# raspi.net
KiCad netlist of a schematic drawn in EAGLE
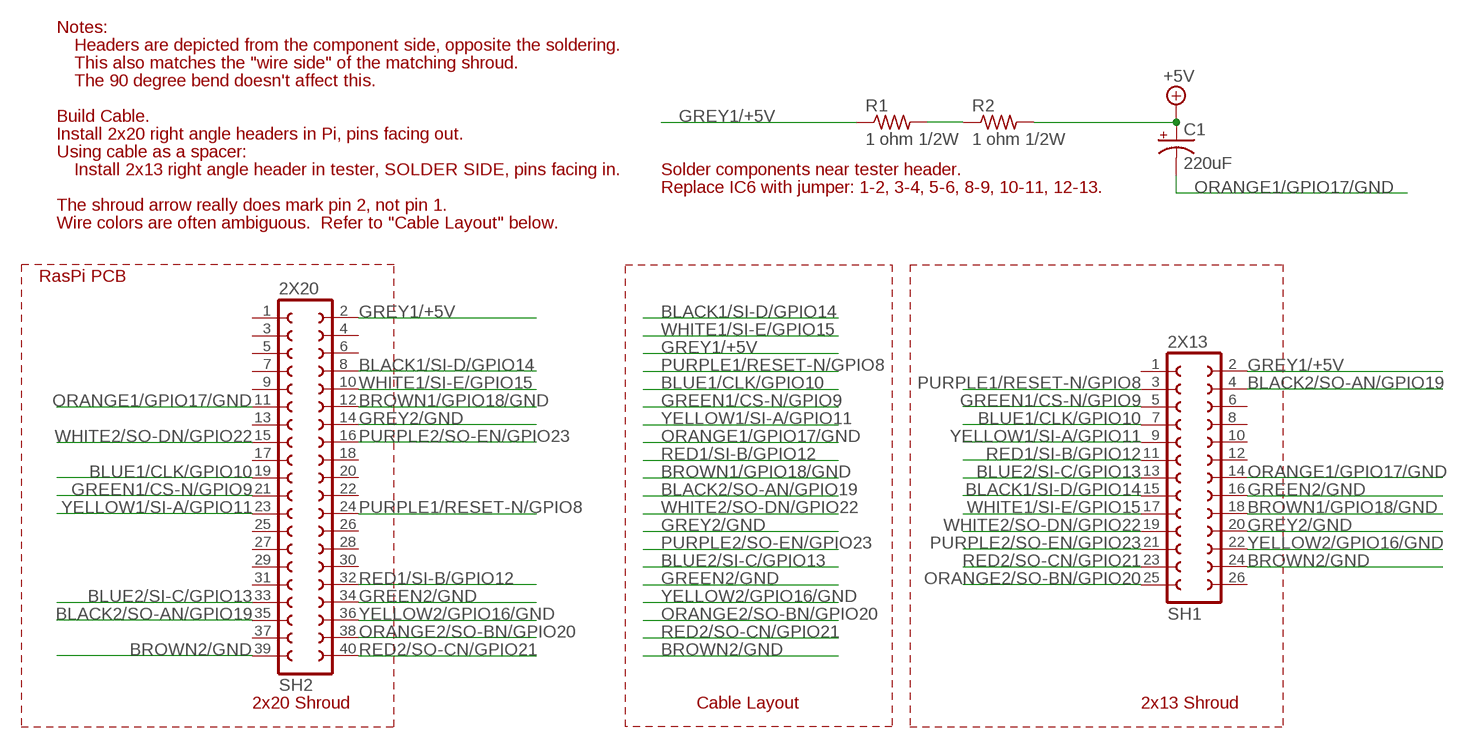
[diagram p0: schematic, sheet 1]

(export (version "E")
  (design (tool "Eeschema 10.0.6"))
  (components
    (comp (ref "C1")
      (value "220uF")
      (footprint "eagle-import:E15-6")
      (libsource (lib "eagle-import") (part "CPOL-USE15-6AXIAL"))
    )
    (comp (ref "R1")
      (value "1 ohm 1/2W")
      (footprint "eagle-import:0207_10")
      (libsource (lib "eagle-import") (part "R-US_0207/10"))
    )
    (comp (ref "R2")
      (value "1 ohm 1/2W")
      (footprint "eagle-import:0207_10")
      (libsource (lib "eagle-import") (part "R-US_0207/10"))
    )
    (comp (ref "SH1")
      (value "2X13")
      (footprint "eagle-import:FE13-2")
      (libsource (lib "eagle-import") (part "FE13-2"))
    )
    (comp (ref "SH2")
      (value "2X20")
      (footprint "eagle-import:FE20-2")
      (libsource (lib "eagle-import") (part "FE20-2"))
    )
  )
  (nets
    (net (code "1") (name "+5V") (class "Default")
      (node (ref "C1") (pin "+") (pinfunction "+_+") (pintype "passive"))
      (node (ref "R2") (pin "2") (pinfunction "2_2") (pintype "passive"))
    )
    (net (code "2") (name "/BLACK1{slash}SI-D{slash}GPIO14") (class "Default")
      (node (ref "SH1") (pin "15") (pinfunction "15_15") (pintype "passive"))
      (node (ref "SH2") (pin "8") (pinfunction "8_8") (pintype "passive"))
    )
    (net (code "3") (name "/BLACK2{slash}SO-AN{slash}GPIO19") (class "Default")
      (node (ref "SH1") (pin "4") (pinfunction "4_4") (pintype "passive"))
      (node (ref "SH2") (pin "35") (pinfunction "35_35") (pintype "passive"))
    )
    (net (code "4") (name "/BLUE1{slash}CLK{slash}GPIO10") (class "Default")
      (node (ref "SH1") (pin "7") (pinfunction "7_7") (pintype "passive"))
      (node (ref "SH2") (pin "19") (pinfunction "19_19") (pintype "passive"))
    )
    (net (code "5") (name "/BLUE2{slash}SI-C{slash}GPIO13") (class "Default")
      (node (ref "SH1") (pin "13") (pinfunction "13_13") (pintype "passive"))
      (node (ref "SH2") (pin "33") (pinfunction "33_33") (pintype "passive"))
    )
    (net (code "6") (name "/BROWN1{slash}GPIO18{slash}GND") (class "Default")
      (node (ref "SH1") (pin "18") (pinfunction "18_18") (pintype "passive"))
      (node (ref "SH2") (pin "12") (pinfunction "12_12") (pintype "passive"))
    )
    (net (code "7") (name "/BROWN2{slash}GND") (class "Default")
      (node (ref "SH1") (pin "24") (pinfunction "24_24") (pintype "passive"))
      (node (ref "SH2") (pin "39") (pinfunction "39_39") (pintype "passive"))
    )
    (net (code "8") (name "/GREEN1{slash}CS-N{slash}GPIO9") (class "Default")
      (node (ref "SH1") (pin "5") (pinfunction "5_5") (pintype "passive"))
      (node (ref "SH2") (pin "21") (pinfunction "21_21") (pintype "passive"))
    )
    (net (code "9") (name "/GREEN2{slash}GND") (class "Default")
      (node (ref "SH1") (pin "16") (pinfunction "16_16") (pintype "passive"))
      (node (ref "SH2") (pin "34") (pinfunction "34_34") (pintype "passive"))
    )
    (net (code "10") (name "/GREY1{slash}+5V") (class "Default")
      (node (ref "R1") (pin "1") (pinfunction "1_1") (pintype "passive"))
      (node (ref "SH1") (pin "2") (pinfunction "2_2") (pintype "passive"))
      (node (ref "SH2") (pin "2") (pinfunction "2_2") (pintype "passive"))
    )
    (net (code "11") (name "/GREY2{slash}GND") (class "Default")
      (node (ref "SH1") (pin "20") (pinfunction "20_20") (pintype "passive"))
      (node (ref "SH2") (pin "14") (pinfunction "14_14") (pintype "passive"))
    )
    (net (code "12") (name "/ORANGE1{slash}GPIO17{slash}GND") (class "Default")
      (node (ref "C1") (pin "-") (pinfunction "-_-") (pintype "passive"))
      (node (ref "SH1") (pin "14") (pinfunction "14_14") (pintype "passive"))
      (node (ref "SH2") (pin "11") (pinfunction "11_11") (pintype "passive"))
    )
    (net (code "13") (name "/ORANGE2{slash}SO-BN{slash}GPIO20") (class "Default")
      (node (ref "SH1") (pin "25") (pinfunction "25_25") (pintype "passive"))
      (node (ref "SH2") (pin "38") (pinfunction "38_38") (pintype "passive"))
    )
    (net (code "14") (name "/PURPLE1{slash}RESET-N{slash}GPIO8") (class "Default")
      (node (ref "SH1") (pin "3") (pinfunction "3_3") (pintype "passive"))
      (node (ref "SH2") (pin "24") (pinfunction "24_24") (pintype "passive"))
    )
    (net (code "15") (name "/PURPLE2{slash}SO-EN{slash}GPIO23") (class "Default")
      (node (ref "SH1") (pin "21") (pinfunction "21_21") (pintype "passive"))
      (node (ref "SH2") (pin "16") (pinfunction "16_16") (pintype "passive"))
    )
    (net (code "16") (name "/RED1{slash}SI-B{slash}GPIO12") (class "Default")
      (node (ref "SH1") (pin "11") (pinfunction "11_11") (pintype "passive"))
      (node (ref "SH2") (pin "32") (pinfunction "32_32") (pintype "passive"))
    )
    (net (code "17") (name "/RED2{slash}SO-CN{slash}GPIO21") (class "Default")
      (node (ref "SH1") (pin "23") (pinfunction "23_23") (pintype "passive"))
      (node (ref "SH2") (pin "40") (pinfunction "40_40") (pintype "passive"))
    )
    (net (code "18") (name "/WHITE1{slash}SI-E{slash}GPIO15") (class "Default")
      (node (ref "SH1") (pin "17") (pinfunction "17_17") (pintype "passive"))
      (node (ref "SH2") (pin "10") (pinfunction "10_10") (pintype "passive"))
    )
    (net (code "19") (name "/WHITE2{slash}SO-DN{slash}GPIO22") (class "Default")
      (node (ref "SH1") (pin "19") (pinfunction "19_19") (pintype "passive"))
      (node (ref "SH2") (pin "15") (pinfunction "15_15") (pintype "passive"))
    )
    (net (code "20") (name "/YELLOW1{slash}SI-A{slash}GPIO11") (class "Default")
      (node (ref "SH1") (pin "9") (pinfunction "9_9") (pintype "passive"))
      (node (ref "SH2") (pin "23") (pinfunction "23_23") (pintype "passive"))
    )
    (net (code "21") (name "/YELLOW2{slash}GPIO16{slash}GND") (class "Default")
      (node (ref "SH1") (pin "22") (pinfunction "22_22") (pintype "passive"))
      (node (ref "SH2") (pin "36") (pinfunction "36_36") (pintype "passive"))
    )
    (net (code "22") (name "Net-(R1-Pad2)") (class "Default")
      (node (ref "R1") (pin "2") (pinfunction "2_2") (pintype "passive"))
      (node (ref "R2") (pin "1") (pinfunction "1_1") (pintype "passive"))
    )
    (net (code "23") (name "unconnected-(SH1-Pad1)") (class "Default")
      (node (ref "SH1") (pin "1") (pinfunction "1_1") (pintype "passive"))
    )
    (net (code "24") (name "unconnected-(SH1-Pad6)") (class "Default")
      (node (ref "SH1") (pin "6") (pinfunction "6_6") (pintype "passive"))
    )
    (net (code "25") (name "unconnected-(SH1-Pad8)") (class "Default")
      (node (ref "SH1") (pin "8") (pinfunction "8_8") (pintype "passive"))
    )
    (net (code "26") (name "unconnected-(SH1-Pad10)") (class "Default")
      (node (ref "SH1") (pin "10") (pinfunction "10_10") (pintype "passive"))
    )
    (net (code "27") (name "unconnected-(SH1-Pad12)") (class "Default")
      (node (ref "SH1") (pin "12") (pinfunction "12_12") (pintype "passive"))
    )
    (net (code "28") (name "unconnected-(SH1-Pad26)") (class "Default")
      (node (ref "SH1") (pin "26") (pinfunction "26_26") (pintype "passive"))
    )
    (net (code "29") (name "unconnected-(SH2-Pad1)") (class "Default")
      (node (ref "SH2") (pin "1") (pinfunction "1_1") (pintype "passive"))
    )
    (net (code "30") (name "unconnected-(SH2-Pad3)") (class "Default")
      (node (ref "SH2") (pin "3") (pinfunction "3_3") (pintype "passive"))
    )
    (net (code "31") (name "unconnected-(SH2-Pad4)") (class "Default")
      (node (ref "SH2") (pin "4") (pinfunction "4_4") (pintype "passive"))
    )
    (net (code "32") (name "unconnected-(SH2-Pad5)") (class "Default")
      (node (ref "SH2") (pin "5") (pinfunction "5_5") (pintype "passive"))
    )
    (net (code "33") (name "unconnected-(SH2-Pad6)") (class "Default")
      (node (ref "SH2") (pin "6") (pinfunction "6_6") (pintype "passive"))
    )
    (net (code "34") (name "unconnected-(SH2-Pad7)") (class "Default")
      (node (ref "SH2") (pin "7") (pinfunction "7_7") (pintype "passive"))
    )
    (net (code "35") (name "unconnected-(SH2-Pad9)") (class "Default")
      (node (ref "SH2") (pin "9") (pinfunction "9_9") (pintype "passive"))
    )
    (net (code "36") (name "unconnected-(SH2-Pad13)") (class "Default")
      (node (ref "SH2") (pin "13") (pinfunction "13_13") (pintype "passive"))
    )
    (net (code "37") (name "unconnected-(SH2-Pad17)") (class "Default")
      (node (ref "SH2") (pin "17") (pinfunction "17_17") (pintype "passive"))
    )
    (net (code "38") (name "unconnected-(SH2-Pad18)") (class "Default")
      (node (ref "SH2") (pin "18") (pinfunction "18_18") (pintype "passive"))
    )
    (net (code "39") (name "unconnected-(SH2-Pad20)") (class "Default")
      (node (ref "SH2") (pin "20") (pinfunction "20_20") (pintype "passive"))
    )
    (net (code "40") (name "unconnected-(SH2-Pad22)") (class "Default")
      (node (ref "SH2") (pin "22") (pinfunction "22_22") (pintype "passive"))
    )
    (net (code "41") (name "unconnected-(SH2-Pad25)") (class "Default")
      (node (ref "SH2") (pin "25") (pinfunction "25_25") (pintype "passive"))
    )
    (net (code "42") (name "unconnected-(SH2-Pad26)") (class "Default")
      (node (ref "SH2") (pin "26") (pinfunction "26_26") (pintype "passive"))
    )
    (net (code "43") (name "unconnected-(SH2-Pad27)") (class "Default")
      (node (ref "SH2") (pin "27") (pinfunction "27_27") (pintype "passive"))
    )
    (net (code "44") (name "unconnected-(SH2-Pad28)") (class "Default")
      (node (ref "SH2") (pin "28") (pinfunction "28_28") (pintype "passive"))
    )
    (net (code "45") (name "unconnected-(SH2-Pad29)") (class "Default")
      (node (ref "SH2") (pin "29") (pinfunction "29_29") (pintype "passive"))
    )
    (net (code "46") (name "unconnected-(SH2-Pad30)") (class "Default")
      (node (ref "SH2") (pin "30") (pinfunction "30_30") (pintype "passive"))
    )
    (net (code "47") (name "unconnected-(SH2-Pad31)") (class "Default")
      (node (ref "SH2") (pin "31") (pinfunction "31_31") (pintype "passive"))
    )
    (net (code "48") (name "unconnected-(SH2-Pad37)") (class "Default")
      (node (ref "SH2") (pin "37") (pinfunction "37_37") (pintype "passive"))
    )
  )
)
